# Servos_Aux_Motors_Board.net
KiCad netlist of a schematic drawn in EAGLE
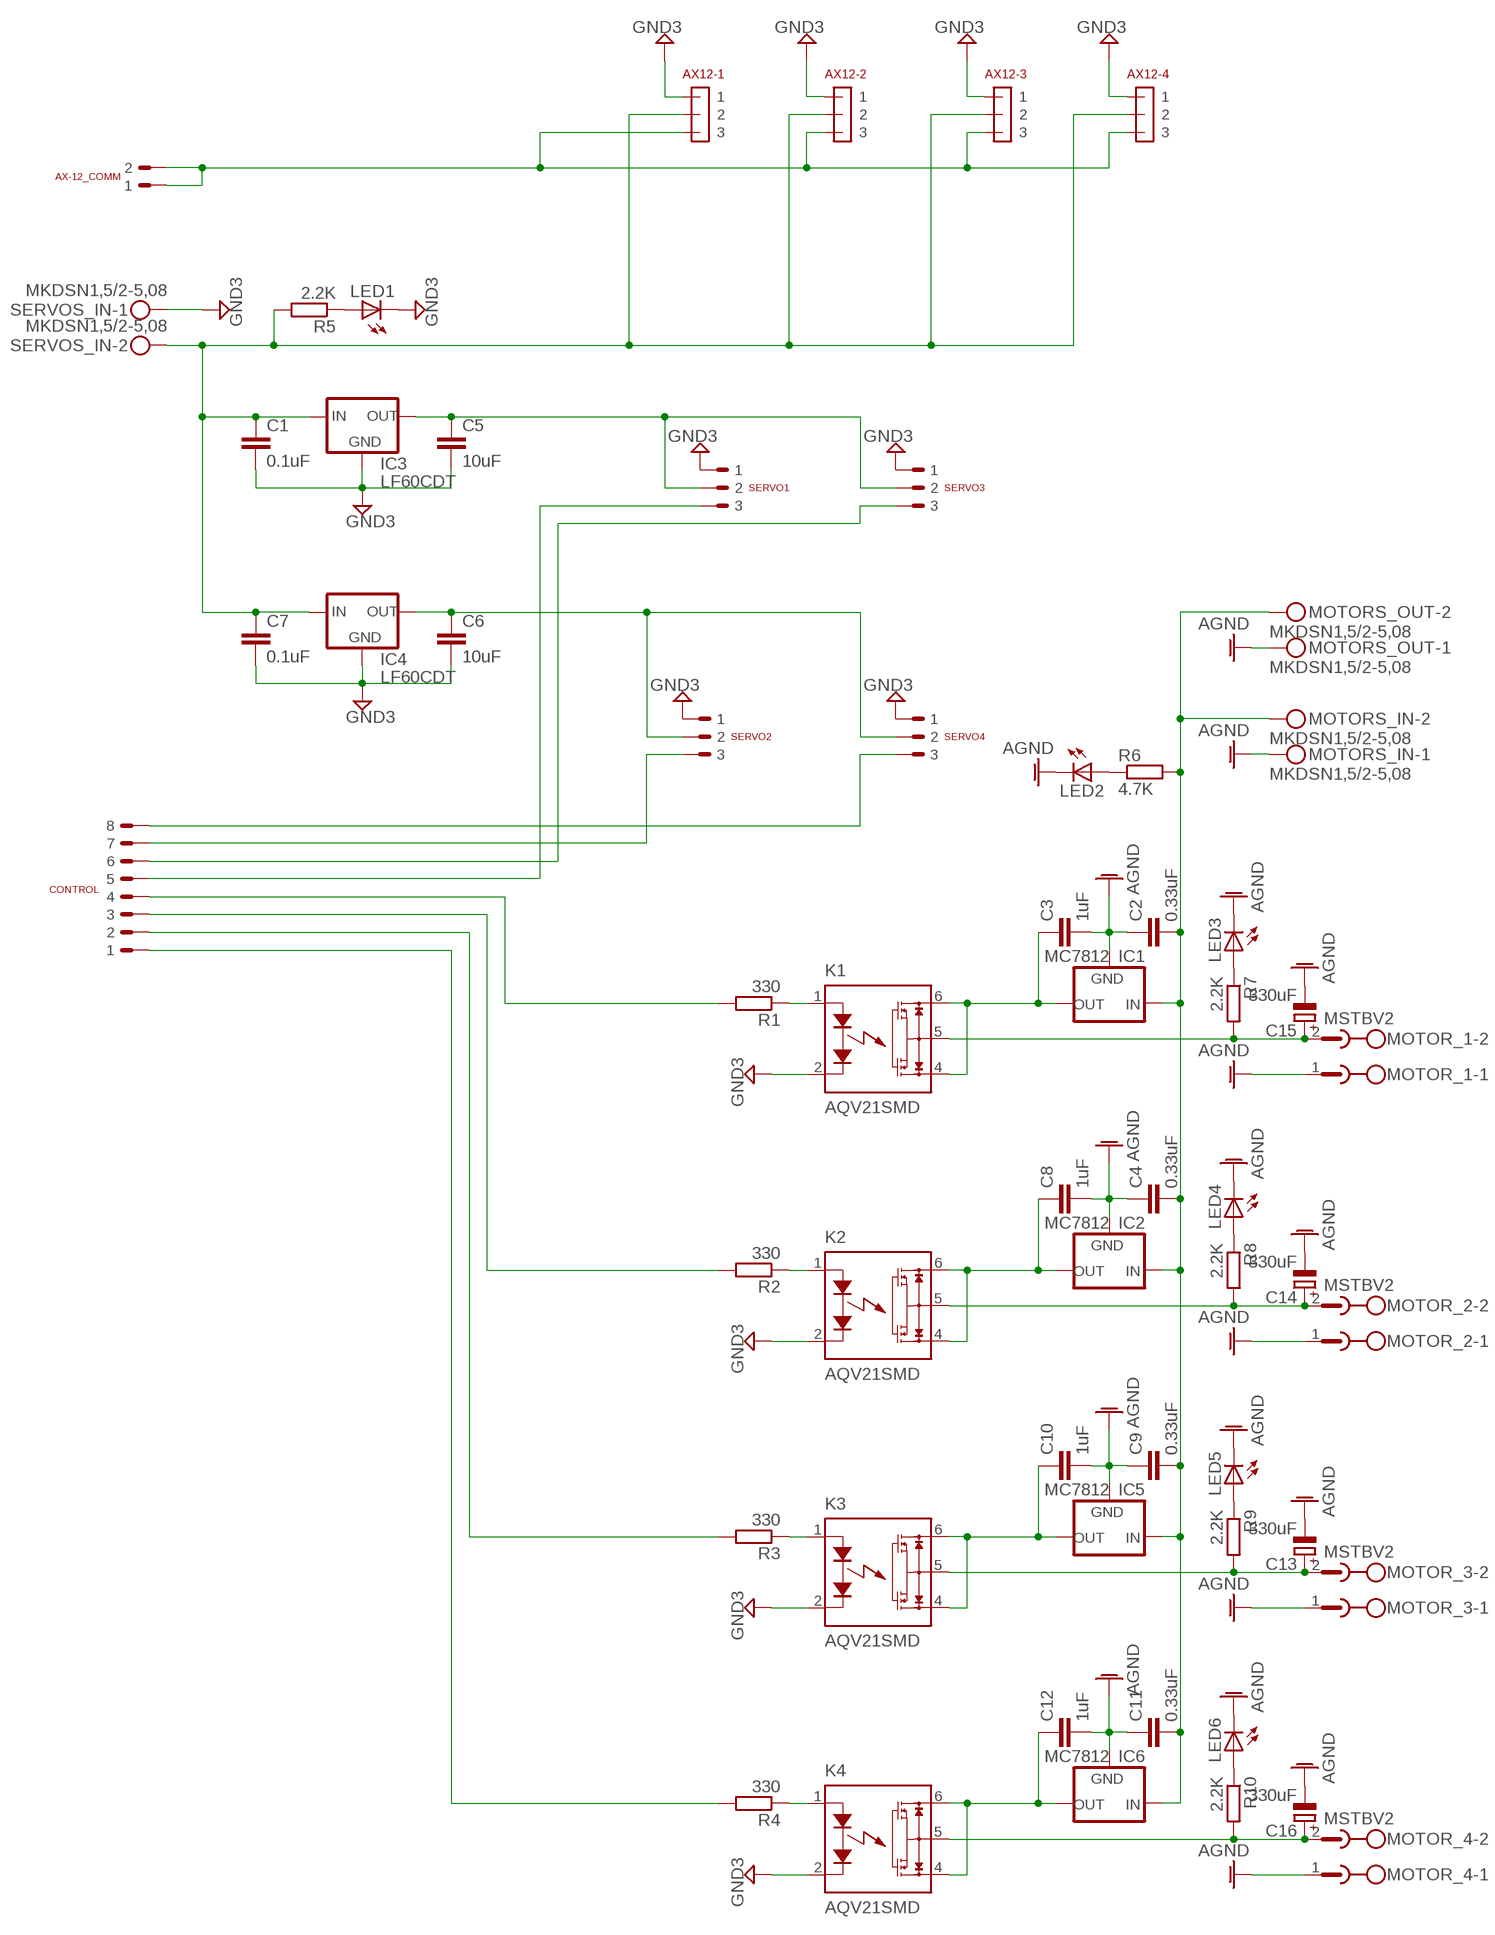
[diagram p0: schematic, sheet 1]

(export (version "E")
  (design (tool "Eeschema 10.0.6"))
  (components
    (comp (ref "AX-12_COMM")
      (value "87437-0243")
      (footprint "eagle-import:87437-0243")
      (libsource (lib "eagle-import") (part "87437-0243"))
    )
    (comp (ref "AX12-1")
      (value "22-03-5035")
      (footprint "eagle-import:22-03-5035")
      (libsource (lib "eagle-import") (part "22-03-5035"))
    )
    (comp (ref "AX12-2")
      (value "22-03-5035")
      (footprint "eagle-import:22-03-5035")
      (libsource (lib "eagle-import") (part "22-03-5035"))
    )
    (comp (ref "AX12-3")
      (value "22-03-5035")
      (footprint "eagle-import:22-03-5035")
      (libsource (lib "eagle-import") (part "22-03-5035"))
    )
    (comp (ref "AX12-4")
      (value "22-03-5035")
      (footprint "eagle-import:22-03-5035")
      (libsource (lib "eagle-import") (part "22-03-5035"))
    )
    (comp (ref "C1")
      (value "0.1uF")
      (footprint "eagle-import:C0603")
      (libsource (lib "eagle-import") (part "C-EUC0603"))
    )
    (comp (ref "C2")
      (value "0.33uF")
      (footprint "eagle-import:C0805")
      (libsource (lib "eagle-import") (part "C-EUC0805"))
    )
    (comp (ref "C3")
      (value "1uF")
      (footprint "eagle-import:C0805")
      (libsource (lib "eagle-import") (part "C-EUC0805"))
    )
    (comp (ref "C4")
      (value "0.33uF")
      (footprint "eagle-import:C0805")
      (libsource (lib "eagle-import") (part "C-EUC0805"))
    )
    (comp (ref "C5")
      (value "10uF")
      (footprint "eagle-import:C0805")
      (libsource (lib "eagle-import") (part "resistor_C-EUC0805"))
    )
    (comp (ref "C6")
      (value "10uF")
      (footprint "eagle-import:C0805")
      (libsource (lib "eagle-import") (part "resistor_C-EUC0805"))
    )
    (comp (ref "C7")
      (value "0.1uF")
      (footprint "eagle-import:C0603")
      (libsource (lib "eagle-import") (part "C-EUC0603"))
    )
    (comp (ref "C8")
      (value "1uF")
      (footprint "eagle-import:C0805")
      (libsource (lib "eagle-import") (part "C-EUC0805"))
    )
    (comp (ref "C9")
      (value "0.33uF")
      (footprint "eagle-import:C0805")
      (libsource (lib "eagle-import") (part "C-EUC0805"))
    )
    (comp (ref "C10")
      (value "1uF")
      (footprint "eagle-import:C0805")
      (libsource (lib "eagle-import") (part "C-EUC0805"))
    )
    (comp (ref "C11")
      (value "0.33uF")
      (footprint "eagle-import:C0805")
      (libsource (lib "eagle-import") (part "C-EUC0805"))
    )
    (comp (ref "C12")
      (value "1uF")
      (footprint "eagle-import:C0805")
      (libsource (lib "eagle-import") (part "C-EUC0805"))
    )
    (comp (ref "C13")
      (value "330uF")
      (footprint "eagle-import:E3,5-8")
      (libsource (lib "eagle-import") (part "CPOL-EUE3.5-8"))
    )
    (comp (ref "C14")
      (value "330uF")
      (footprint "eagle-import:E3,5-8")
      (libsource (lib "eagle-import") (part "CPOL-EUE3.5-8"))
    )
    (comp (ref "C15")
      (value "330uF")
      (footprint "eagle-import:E3,5-8")
      (libsource (lib "eagle-import") (part "CPOL-EUE3.5-8"))
    )
    (comp (ref "C16")
      (value "330uF")
      (footprint "eagle-import:E3,5-8")
      (libsource (lib "eagle-import") (part "CPOL-EUE3.5-8"))
    )
    (comp (ref "CONTROL")
      (value "87437-0843")
      (footprint "eagle-import:87437-0843")
      (libsource (lib "eagle-import") (part "87437-0843"))
    )
    (comp (ref "IC1")
      (value "MC7812")
      (footprint "eagle-import:DPACK")
      (libsource (lib "eagle-import") (part "LP2950?CDT-5.0"))
    )
    (comp (ref "IC2")
      (value "MC7812")
      (footprint "eagle-import:DPACK")
      (libsource (lib "eagle-import") (part "LP2950?CDT-5.0"))
    )
    (comp (ref "IC3")
      (value "LF60CDT")
      (footprint "eagle-import:DPACK")
      (libsource (lib "eagle-import") (part "LP2950?CDT-5.0"))
    )
    (comp (ref "IC4")
      (value "LF60CDT")
      (footprint "eagle-import:DPACK")
      (libsource (lib "eagle-import") (part "LP2950?CDT-5.0"))
    )
    (comp (ref "IC5")
      (value "MC7812")
      (footprint "eagle-import:DPACK")
      (libsource (lib "eagle-import") (part "LP2950?CDT-5.0"))
    )
    (comp (ref "IC6")
      (value "MC7812")
      (footprint "eagle-import:DPACK")
      (libsource (lib "eagle-import") (part "LP2950?CDT-5.0"))
    )
    (comp (ref "K1")
      (value "AQV21SMD")
      (footprint "eagle-import:DIL06SMD")
      (fields (field (name "MF") "AROMAT/ MATSUSHITA") (field (name "MPN") "AQV210S"))
      (libsource (lib "eagle-import") (part "AQVSMD21"))
    )
    (comp (ref "K2")
      (value "AQV21SMD")
      (footprint "eagle-import:DIL06SMD")
      (fields (field (name "MF") "AROMAT/ MATSUSHITA") (field (name "MPN") "AQV210S"))
      (libsource (lib "eagle-import") (part "AQVSMD21"))
    )
    (comp (ref "K3")
      (value "AQV21SMD")
      (footprint "eagle-import:DIL06SMD")
      (fields (field (name "MF") "AROMAT/ MATSUSHITA") (field (name "MPN") "AQV210S"))
      (libsource (lib "eagle-import") (part "AQVSMD21"))
    )
    (comp (ref "K4")
      (value "AQV21SMD")
      (footprint "eagle-import:DIL06SMD")
      (fields (field (name "MF") "AROMAT/ MATSUSHITA") (field (name "MPN") "AQV210S"))
      (libsource (lib "eagle-import") (part "AQVSMD21"))
    )
    (comp (ref "LED1")
      (value "LEDCHIP-LED0603")
      (footprint "eagle-import:CHIP-LED0603")
      (libsource (lib "eagle-import") (part "LEDCHIP-LED0603"))
    )
    (comp (ref "LED2")
      (value "LEDCHIP-LED0603")
      (footprint "eagle-import:CHIP-LED0603")
      (libsource (lib "eagle-import") (part "LEDCHIP-LED0603"))
    )
    (comp (ref "LED3")
      (value "LEDCHIP-LED0603")
      (footprint "eagle-import:CHIP-LED0603")
      (libsource (lib "eagle-import") (part "LEDCHIP-LED0603"))
    )
    (comp (ref "LED4")
      (value "LEDCHIP-LED0603")
      (footprint "eagle-import:CHIP-LED0603")
      (libsource (lib "eagle-import") (part "LEDCHIP-LED0603"))
    )
    (comp (ref "LED5")
      (value "LEDCHIP-LED0603")
      (footprint "eagle-import:CHIP-LED0603")
      (libsource (lib "eagle-import") (part "LEDCHIP-LED0603"))
    )
    (comp (ref "LED6")
      (value "LEDCHIP-LED0603")
      (footprint "eagle-import:CHIP-LED0603")
      (libsource (lib "eagle-import") (part "LEDCHIP-LED0603"))
    )
    (comp (ref "MOTORS_IN")
      (value "MKDSN1,5/2-5,08")
      (footprint "eagle-import:MKDSN1,5_2-5,08")
      (fields (field (name "MPN") "MKDSN 1,5/2-5.08"))
      (libsource (lib "eagle-import") (part "MKDSN1,5/2-5,08"))
    )
    (comp (ref "MOTORS_OUT")
      (value "MKDSN1,5/2-5,08")
      (footprint "eagle-import:MKDSN1,5_2-5,08")
      (fields (field (name "MPN") "MKDSN 1,5/2-5.08"))
      (libsource (lib "eagle-import") (part "MKDSN1,5/2-5,08"))
    )
    (comp (ref "MOTOR_1")
      (value "MSTBV2")
      (footprint "eagle-import:MSTBV2")
      (fields (field (name "MPN") "MSTBV 2,5/2-GF-5.08"))
      (libsource (lib "eagle-import") (part "MSTBV2"))
    )
    (comp (ref "MOTOR_2")
      (value "MSTBV2")
      (footprint "eagle-import:MSTBV2")
      (fields (field (name "MPN") "MSTBV 2,5/2-GF-5.08"))
      (libsource (lib "eagle-import") (part "MSTBV2"))
    )
    (comp (ref "MOTOR_3")
      (value "MSTBV2")
      (footprint "eagle-import:MSTBV2")
      (fields (field (name "MPN") "MSTBV 2,5/2-GF-5.08"))
      (libsource (lib "eagle-import") (part "MSTBV2"))
    )
    (comp (ref "MOTOR_4")
      (value "MSTBV2")
      (footprint "eagle-import:MSTBV2")
      (fields (field (name "MPN") "MSTBV 2,5/2-GF-5.08"))
      (libsource (lib "eagle-import") (part "MSTBV2"))
    )
    (comp (ref "R1")
      (value "330")
      (footprint "eagle-import:R0603")
      (libsource (lib "eagle-import") (part "R-EU_R0603"))
    )
    (comp (ref "R2")
      (value "330")
      (footprint "eagle-import:R0603")
      (libsource (lib "eagle-import") (part "R-EU_R0603"))
    )
    (comp (ref "R3")
      (value "330")
      (footprint "eagle-import:R0603")
      (libsource (lib "eagle-import") (part "R-EU_R0603"))
    )
    (comp (ref "R4")
      (value "330")
      (footprint "eagle-import:R0603")
      (libsource (lib "eagle-import") (part "R-EU_R0603"))
    )
    (comp (ref "R5")
      (value "2.2K")
      (footprint "eagle-import:R0805")
      (libsource (lib "eagle-import") (part "R-EU_R0805"))
    )
    (comp (ref "R6")
      (value "4.7K")
      (footprint "eagle-import:R1206")
      (libsource (lib "eagle-import") (part "R-EU_R1206"))
    )
    (comp (ref "R7")
      (value "2.2K")
      (footprint "eagle-import:R0805")
      (libsource (lib "eagle-import") (part "R-EU_R0805"))
    )
    (comp (ref "R8")
      (value "2.2K")
      (footprint "eagle-import:R0805")
      (libsource (lib "eagle-import") (part "R-EU_R0805"))
    )
    (comp (ref "R9")
      (value "2.2K")
      (footprint "eagle-import:R0805")
      (libsource (lib "eagle-import") (part "R-EU_R0805"))
    )
    (comp (ref "R10")
      (value "2.2K")
      (footprint "eagle-import:R0805")
      (libsource (lib "eagle-import") (part "R-EU_R0805"))
    )
    (comp (ref "SERVO1")
      (value "87437-0343")
      (footprint "eagle-import:87437-0343")
      (libsource (lib "eagle-import") (part "87437-0343"))
    )
    (comp (ref "SERVO2")
      (value "87437-0343")
      (footprint "eagle-import:87437-0343")
      (libsource (lib "eagle-import") (part "87437-0343"))
    )
    (comp (ref "SERVO3")
      (value "87437-0343")
      (footprint "eagle-import:87437-0343")
      (libsource (lib "eagle-import") (part "87437-0343"))
    )
    (comp (ref "SERVO4")
      (value "87437-0343")
      (footprint "eagle-import:87437-0343")
      (libsource (lib "eagle-import") (part "87437-0343"))
    )
    (comp (ref "SERVOS_IN")
      (value "MKDSN1,5/2-5,08")
      (footprint "eagle-import:MKDSN1,5_2-5,08")
      (fields (field (name "MPN") "MKDSN 1,5/2-5.08"))
      (libsource (lib "eagle-import") (part "MKDSN1,5/2-5,08"))
    )
  )
  (nets
    (net (code "1") (name "AGND") (class "Default")
      (node (ref "C10") (pin "2") (pinfunction "2_2") (pintype "passive"))
      (node (ref "C11") (pin "1") (pinfunction "1_1") (pintype "passive"))
      (node (ref "C12") (pin "2") (pinfunction "2_2") (pintype "passive"))
      (node (ref "C13") (pin "-") (pinfunction "-_-") (pintype "passive"))
      (node (ref "C14") (pin "-") (pinfunction "-_-") (pintype "passive"))
      (node (ref "C15") (pin "-") (pinfunction "-_-") (pintype "passive"))
      (node (ref "C16") (pin "-") (pinfunction "-_-") (pintype "passive"))
      (node (ref "C2") (pin "1") (pinfunction "1_1") (pintype "passive"))
      (node (ref "C3") (pin "2") (pinfunction "2_2") (pintype "passive"))
      (node (ref "C4") (pin "1") (pinfunction "1_1") (pintype "passive"))
      (node (ref "C8") (pin "2") (pinfunction "2_2") (pintype "passive"))
      (node (ref "C9") (pin "1") (pinfunction "1_1") (pintype "passive"))
      (node (ref "IC1") (pin "4") (pinfunction "GND_4") (pintype "input"))
      (node (ref "IC2") (pin "4") (pinfunction "GND_4") (pintype "input"))
      (node (ref "IC5") (pin "4") (pinfunction "GND_4") (pintype "input"))
      (node (ref "IC6") (pin "4") (pinfunction "GND_4") (pintype "input"))
      (node (ref "LED2") (pin "C") (pinfunction "C_C") (pintype "passive"))
      (node (ref "LED3") (pin "C") (pinfunction "C_C") (pintype "passive"))
      (node (ref "LED4") (pin "C") (pinfunction "C_C") (pintype "passive"))
      (node (ref "LED5") (pin "C") (pinfunction "C_C") (pintype "passive"))
      (node (ref "LED6") (pin "C") (pinfunction "C_C") (pintype "passive"))
      (node (ref "MOTORS_IN") (pin "1") (pinfunction "KL_1") (pintype "passive"))
      (node (ref "MOTORS_OUT") (pin "1") (pinfunction "KL_1") (pintype "passive"))
      (node (ref "MOTOR_1") (pin "1") (pinfunction "1_1") (pintype "passive"))
      (node (ref "MOTOR_2") (pin "1") (pinfunction "1_1") (pintype "passive"))
      (node (ref "MOTOR_3") (pin "1") (pinfunction "1_1") (pintype "passive"))
      (node (ref "MOTOR_4") (pin "1") (pinfunction "1_1") (pintype "passive"))
    )
    (net (code "2") (name "GND3") (class "Default")
      (node (ref "AX12-1") (pin "P$1") (pinfunction "1_P$1") (pintype "bidirectional"))
      (node (ref "AX12-2") (pin "P$1") (pinfunction "1_P$1") (pintype "bidirectional"))
      (node (ref "AX12-3") (pin "P$1") (pinfunction "1_P$1") (pintype "bidirectional"))
      (node (ref "AX12-4") (pin "P$1") (pinfunction "1_P$1") (pintype "bidirectional"))
      (node (ref "C1") (pin "2") (pinfunction "2_2") (pintype "passive"))
      (node (ref "C5") (pin "2") (pinfunction "2_2") (pintype "passive"))
      (node (ref "C6") (pin "2") (pinfunction "2_2") (pintype "passive"))
      (node (ref "C7") (pin "2") (pinfunction "2_2") (pintype "passive"))
      (node (ref "IC3") (pin "4") (pinfunction "GND_4") (pintype "input"))
      (node (ref "IC4") (pin "4") (pinfunction "GND_4") (pintype "input"))
      (node (ref "K1") (pin "2") (pinfunction "K_2") (pintype "passive"))
      (node (ref "K2") (pin "2") (pinfunction "K_2") (pintype "passive"))
      (node (ref "K3") (pin "2") (pinfunction "K_2") (pintype "passive"))
      (node (ref "K4") (pin "2") (pinfunction "K_2") (pintype "passive"))
      (node (ref "LED1") (pin "C") (pinfunction "C_C") (pintype "passive"))
      (node (ref "SERVO1") (pin "P$1") (pinfunction "1_P$1") (pintype "bidirectional"))
      (node (ref "SERVO2") (pin "P$1") (pinfunction "1_P$1") (pintype "bidirectional"))
      (node (ref "SERVO3") (pin "P$1") (pinfunction "1_P$1") (pintype "bidirectional"))
      (node (ref "SERVO4") (pin "P$1") (pinfunction "1_P$1") (pintype "bidirectional"))
      (node (ref "SERVOS_IN") (pin "1") (pinfunction "KL_1") (pintype "passive"))
    )
    (net (code "3") (name "Net-(AX-12_COMM-1)") (class "Default")
      (node (ref "AX-12_COMM") (pin "P$1") (pinfunction "1_P$1") (pintype "bidirectional"))
      (node (ref "AX-12_COMM") (pin "P$2") (pinfunction "2_P$2") (pintype "bidirectional"))
      (node (ref "AX12-1") (pin "P$3") (pinfunction "3_P$3") (pintype "bidirectional"))
      (node (ref "AX12-2") (pin "P$3") (pinfunction "3_P$3") (pintype "bidirectional"))
      (node (ref "AX12-3") (pin "P$3") (pinfunction "3_P$3") (pintype "bidirectional"))
      (node (ref "AX12-4") (pin "P$3") (pinfunction "3_P$3") (pintype "bidirectional"))
    )
    (net (code "4") (name "Net-(AX12-1-2)") (class "Default")
      (node (ref "AX12-1") (pin "P$2") (pinfunction "2_P$2") (pintype "bidirectional"))
      (node (ref "AX12-2") (pin "P$2") (pinfunction "2_P$2") (pintype "bidirectional"))
      (node (ref "AX12-3") (pin "P$2") (pinfunction "2_P$2") (pintype "bidirectional"))
      (node (ref "AX12-4") (pin "P$2") (pinfunction "2_P$2") (pintype "bidirectional"))
      (node (ref "C1") (pin "1") (pinfunction "1_1") (pintype "passive"))
      (node (ref "C7") (pin "1") (pinfunction "1_1") (pintype "passive"))
      (node (ref "IC3") (pin "1") (pinfunction "IN_1") (pintype "input"))
      (node (ref "IC4") (pin "1") (pinfunction "IN_1") (pintype "input"))
      (node (ref "R5") (pin "2") (pinfunction "2_2") (pintype "passive"))
      (node (ref "SERVOS_IN") (pin "2") (pinfunction "KL_2") (pintype "passive"))
    )
    (net (code "5") (name "Net-(CONTROL-1)") (class "Default")
      (node (ref "CONTROL") (pin "P$1") (pinfunction "1_P$1") (pintype "bidirectional"))
      (node (ref "R4") (pin "2") (pinfunction "2_2") (pintype "passive"))
    )
    (net (code "6") (name "Net-(CONTROL-2)") (class "Default")
      (node (ref "CONTROL") (pin "P$2") (pinfunction "2_P$2") (pintype "bidirectional"))
      (node (ref "R3") (pin "2") (pinfunction "2_2") (pintype "passive"))
    )
    (net (code "7") (name "Net-(CONTROL-3)") (class "Default")
      (node (ref "CONTROL") (pin "P$3") (pinfunction "3_P$3") (pintype "bidirectional"))
      (node (ref "R2") (pin "2") (pinfunction "2_2") (pintype "passive"))
    )
    (net (code "8") (name "Net-(CONTROL-4)") (class "Default")
      (node (ref "CONTROL") (pin "P$4") (pinfunction "4_P$4") (pintype "bidirectional"))
      (node (ref "R1") (pin "2") (pinfunction "2_2") (pintype "passive"))
    )
    (net (code "9") (name "Net-(CONTROL-5)") (class "Default")
      (node (ref "CONTROL") (pin "P$5") (pinfunction "5_P$5") (pintype "bidirectional"))
      (node (ref "SERVO1") (pin "P$3") (pinfunction "3_P$3") (pintype "bidirectional"))
    )
    (net (code "10") (name "Net-(CONTROL-6)") (class "Default")
      (node (ref "CONTROL") (pin "P$6") (pinfunction "6_P$6") (pintype "bidirectional"))
      (node (ref "SERVO3") (pin "P$3") (pinfunction "3_P$3") (pintype "bidirectional"))
    )
    (net (code "11") (name "Net-(CONTROL-7)") (class "Default")
      (node (ref "CONTROL") (pin "P$7") (pinfunction "7_P$7") (pintype "bidirectional"))
      (node (ref "SERVO2") (pin "P$3") (pinfunction "3_P$3") (pintype "bidirectional"))
    )
    (net (code "12") (name "Net-(CONTROL-8)") (class "Default")
      (node (ref "CONTROL") (pin "P$8") (pinfunction "8_P$8") (pintype "bidirectional"))
      (node (ref "SERVO4") (pin "P$3") (pinfunction "3_P$3") (pintype "bidirectional"))
    )
    (net (code "13") (name "Net-(IC1-IN)") (class "Default")
      (node (ref "C11") (pin "2") (pinfunction "2_2") (pintype "passive"))
      (node (ref "C2") (pin "2") (pinfunction "2_2") (pintype "passive"))
      (node (ref "C4") (pin "2") (pinfunction "2_2") (pintype "passive"))
      (node (ref "C9") (pin "2") (pinfunction "2_2") (pintype "passive"))
      (node (ref "IC1") (pin "1") (pinfunction "IN_1") (pintype "input"))
      (node (ref "IC2") (pin "1") (pinfunction "IN_1") (pintype "input"))
      (node (ref "IC5") (pin "1") (pinfunction "IN_1") (pintype "input"))
      (node (ref "IC6") (pin "1") (pinfunction "IN_1") (pintype "input"))
      (node (ref "MOTORS_IN") (pin "2") (pinfunction "KL_2") (pintype "passive"))
      (node (ref "MOTORS_OUT") (pin "2") (pinfunction "KL_2") (pintype "passive"))
      (node (ref "R6") (pin "2") (pinfunction "2_2") (pintype "passive"))
    )
    (net (code "14") (name "Net-(IC1-OUT)") (class "Default")
      (node (ref "C3") (pin "1") (pinfunction "1_1") (pintype "passive"))
      (node (ref "IC1") (pin "3") (pinfunction "OUT_3") (pintype "passive"))
      (node (ref "K1") (pin "4") (pinfunction "D2_4") (pintype "passive"))
      (node (ref "K1") (pin "6") (pinfunction "D1_6") (pintype "passive"))
    )
    (net (code "15") (name "Net-(IC2-OUT)") (class "Default")
      (node (ref "C8") (pin "1") (pinfunction "1_1") (pintype "passive"))
      (node (ref "IC2") (pin "3") (pinfunction "OUT_3") (pintype "passive"))
      (node (ref "K2") (pin "4") (pinfunction "D2_4") (pintype "passive"))
      (node (ref "K2") (pin "6") (pinfunction "D1_6") (pintype "passive"))
    )
    (net (code "16") (name "Net-(IC3-OUT)") (class "Default")
      (node (ref "C5") (pin "1") (pinfunction "1_1") (pintype "passive"))
      (node (ref "IC3") (pin "3") (pinfunction "OUT_3") (pintype "passive"))
      (node (ref "SERVO1") (pin "P$2") (pinfunction "2_P$2") (pintype "bidirectional"))
      (node (ref "SERVO3") (pin "P$2") (pinfunction "2_P$2") (pintype "bidirectional"))
    )
    (net (code "17") (name "Net-(IC4-OUT)") (class "Default")
      (node (ref "C6") (pin "1") (pinfunction "1_1") (pintype "passive"))
      (node (ref "IC4") (pin "3") (pinfunction "OUT_3") (pintype "passive"))
      (node (ref "SERVO2") (pin "P$2") (pinfunction "2_P$2") (pintype "bidirectional"))
      (node (ref "SERVO4") (pin "P$2") (pinfunction "2_P$2") (pintype "bidirectional"))
    )
    (net (code "18") (name "Net-(IC5-OUT)") (class "Default")
      (node (ref "C10") (pin "1") (pinfunction "1_1") (pintype "passive"))
      (node (ref "IC5") (pin "3") (pinfunction "OUT_3") (pintype "passive"))
      (node (ref "K3") (pin "4") (pinfunction "D2_4") (pintype "passive"))
      (node (ref "K3") (pin "6") (pinfunction "D1_6") (pintype "passive"))
    )
    (net (code "19") (name "Net-(IC6-OUT)") (class "Default")
      (node (ref "C12") (pin "1") (pinfunction "1_1") (pintype "passive"))
      (node (ref "IC6") (pin "3") (pinfunction "OUT_3") (pintype "passive"))
      (node (ref "K4") (pin "4") (pinfunction "D2_4") (pintype "passive"))
      (node (ref "K4") (pin "6") (pinfunction "D1_6") (pintype "passive"))
    )
    (net (code "20") (name "Net-(K1-A)") (class "Default")
      (node (ref "K1") (pin "1") (pinfunction "A_1") (pintype "passive"))
      (node (ref "R1") (pin "1") (pinfunction "1_1") (pintype "passive"))
    )
    (net (code "21") (name "Net-(K1-S)") (class "Default")
      (node (ref "C15") (pin "+") (pinfunction "+_+") (pintype "passive"))
      (node (ref "K1") (pin "5") (pinfunction "S_5") (pintype "passive"))
      (node (ref "MOTOR_1") (pin "2") (pinfunction "1_2") (pintype "passive"))
      (node (ref "R7") (pin "2") (pinfunction "2_2") (pintype "passive"))
    )
    (net (code "22") (name "Net-(K2-A)") (class "Default")
      (node (ref "K2") (pin "1") (pinfunction "A_1") (pintype "passive"))
      (node (ref "R2") (pin "1") (pinfunction "1_1") (pintype "passive"))
    )
    (net (code "23") (name "Net-(K2-S)") (class "Default")
      (node (ref "C14") (pin "+") (pinfunction "+_+") (pintype "passive"))
      (node (ref "K2") (pin "5") (pinfunction "S_5") (pintype "passive"))
      (node (ref "MOTOR_2") (pin "2") (pinfunction "1_2") (pintype "passive"))
      (node (ref "R8") (pin "2") (pinfunction "2_2") (pintype "passive"))
    )
    (net (code "24") (name "Net-(K3-A)") (class "Default")
      (node (ref "K3") (pin "1") (pinfunction "A_1") (pintype "passive"))
      (node (ref "R3") (pin "1") (pinfunction "1_1") (pintype "passive"))
    )
    (net (code "25") (name "Net-(K3-S)") (class "Default")
      (node (ref "C13") (pin "+") (pinfunction "+_+") (pintype "passive"))
      (node (ref "K3") (pin "5") (pinfunction "S_5") (pintype "passive"))
      (node (ref "MOTOR_3") (pin "2") (pinfunction "1_2") (pintype "passive"))
      (node (ref "R9") (pin "2") (pinfunction "2_2") (pintype "passive"))
    )
    (net (code "26") (name "Net-(K4-A)") (class "Default")
      (node (ref "K4") (pin "1") (pinfunction "A_1") (pintype "passive"))
      (node (ref "R4") (pin "1") (pinfunction "1_1") (pintype "passive"))
    )
    (net (code "27") (name "Net-(K4-S)") (class "Default")
      (node (ref "C16") (pin "+") (pinfunction "+_+") (pintype "passive"))
      (node (ref "K4") (pin "5") (pinfunction "S_5") (pintype "passive"))
      (node (ref "MOTOR_4") (pin "2") (pinfunction "1_2") (pintype "passive"))
      (node (ref "R10") (pin "2") (pinfunction "2_2") (pintype "passive"))
    )
    (net (code "28") (name "Net-(LED1-PadA)") (class "Default")
      (node (ref "LED1") (pin "A") (pinfunction "A_A") (pintype "passive"))
      (node (ref "R5") (pin "1") (pinfunction "1_1") (pintype "passive"))
    )
    (net (code "29") (name "Net-(LED2-PadA)") (class "Default")
      (node (ref "LED2") (pin "A") (pinfunction "A_A") (pintype "passive"))
      (node (ref "R6") (pin "1") (pinfunction "1_1") (pintype "passive"))
    )
    (net (code "30") (name "Net-(LED3-PadA)") (class "Default")
      (node (ref "LED3") (pin "A") (pinfunction "A_A") (pintype "passive"))
      (node (ref "R7") (pin "1") (pinfunction "1_1") (pintype "passive"))
    )
    (net (code "31") (name "Net-(LED4-PadA)") (class "Default")
      (node (ref "LED4") (pin "A") (pinfunction "A_A") (pintype "passive"))
      (node (ref "R8") (pin "1") (pinfunction "1_1") (pintype "passive"))
    )
    (net (code "32") (name "Net-(LED5-PadA)") (class "Default")
      (node (ref "LED5") (pin "A") (pinfunction "A_A") (pintype "passive"))
      (node (ref "R9") (pin "1") (pinfunction "1_1") (pintype "passive"))
    )
    (net (code "33") (name "Net-(LED6-PadA)") (class "Default")
      (node (ref "LED6") (pin "A") (pinfunction "A_A") (pintype "passive"))
      (node (ref "R10") (pin "1") (pinfunction "1_1") (pintype "passive"))
    )
  )
)
